# 17_-ETH_CONNECTOR.net
KiCad netlist of a schematic drawn in Altium Designer
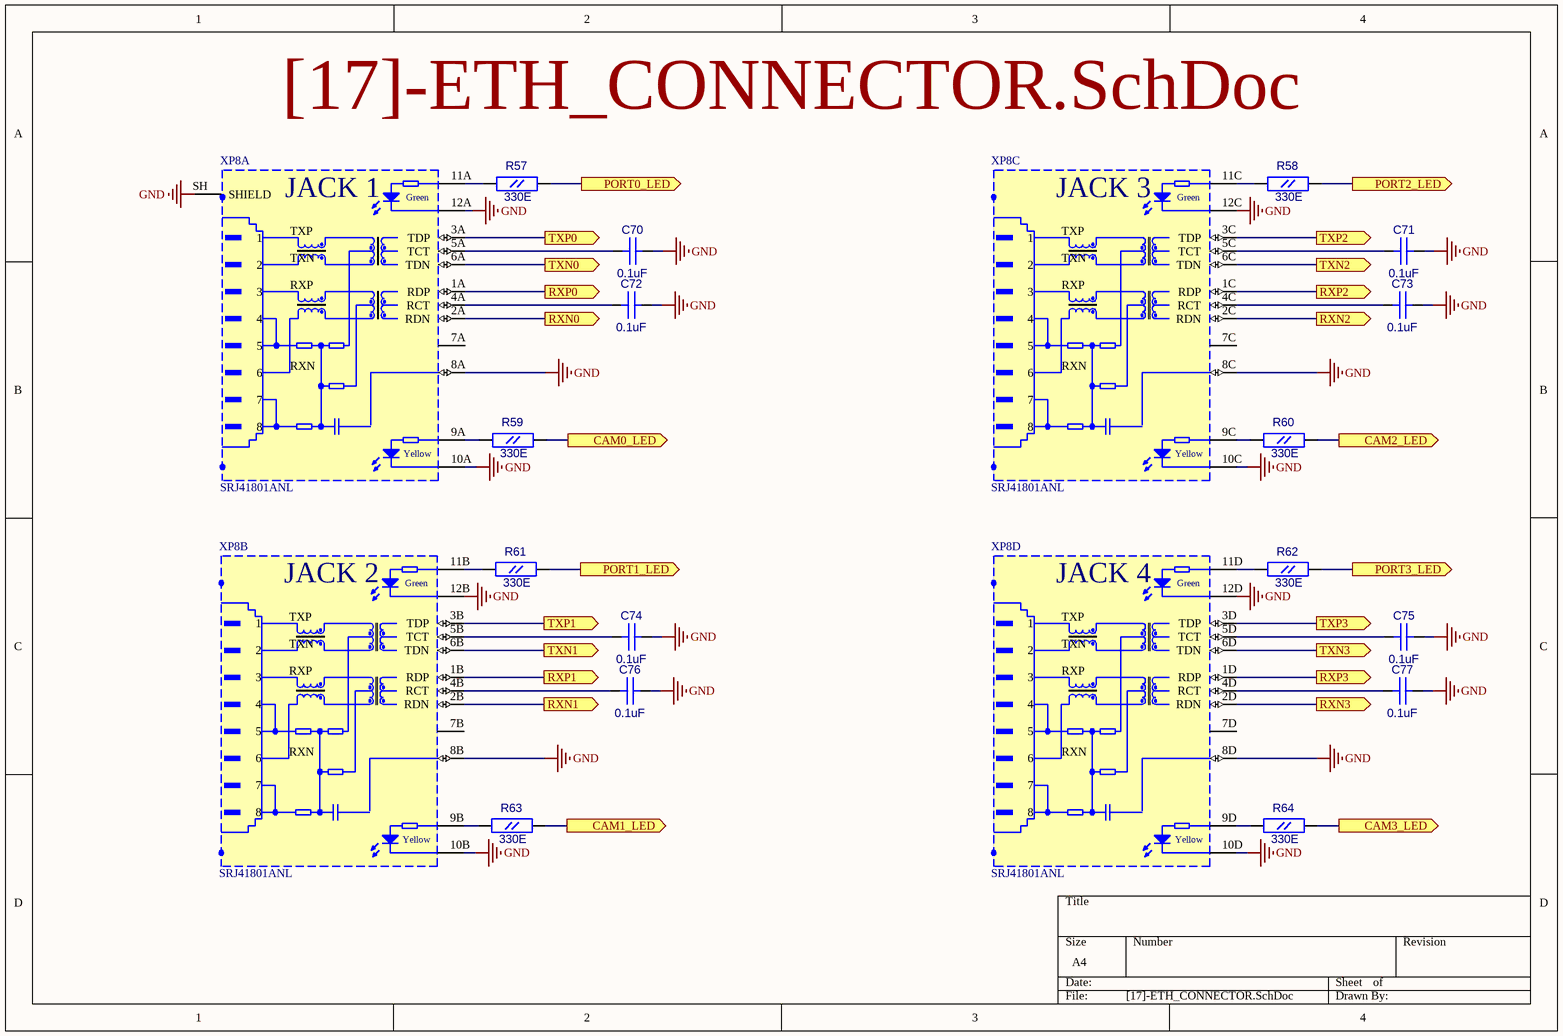
[diagram p0: [17]-ETH_CONNECTOR.SchDoc]

(export (version "E")
  (design (tool "Eeschema 10.0.6"))
  (components
    (comp (ref "C70")
      (value "0.1uF")
      (footprint "CC0603")
      (description "CC0603")
      (libsource (lib "fizik_lib") (part "CC0603"))
    )
    (comp (ref "C71")
      (value "0.1uF")
      (footprint "CC0603")
      (description "CC0603")
      (libsource (lib "fizik_lib") (part "CC0603"))
    )
    (comp (ref "C72")
      (value "0.1uF")
      (footprint "CC0603")
      (description "CC0603")
      (libsource (lib "fizik_lib") (part "CC0603"))
    )
    (comp (ref "C73")
      (value "0.1uF")
      (footprint "CC0603")
      (description "CC0603")
      (libsource (lib "fizik_lib") (part "CC0603"))
    )
    (comp (ref "C74")
      (value "0.1uF")
      (footprint "CC0603")
      (description "CC0603")
      (libsource (lib "fizik_lib") (part "CC0603"))
    )
    (comp (ref "C75")
      (value "0.1uF")
      (footprint "CC0603")
      (description "CC0603")
      (libsource (lib "fizik_lib") (part "CC0603"))
    )
    (comp (ref "C76")
      (value "0.1uF")
      (footprint "CC0603")
      (description "CC0603")
      (libsource (lib "fizik_lib") (part "CC0603"))
    )
    (comp (ref "C77")
      (value "0.1uF")
      (footprint "CC0603")
      (description "CC0603")
      (libsource (lib "fizik_lib") (part "CC0603"))
    )
    (comp (ref "R57")
      (value "330E")
      (footprint "RC0603")
      (description "RC0603")
      (libsource (lib "fizik_lib") (part "RC0603"))
    )
    (comp (ref "R58")
      (value "330E")
      (footprint "RC0603")
      (description "RC0603")
      (libsource (lib "fizik_lib") (part "RC0603"))
    )
    (comp (ref "R59")
      (value "330E")
      (footprint "RC0603")
      (description "RC0603")
      (libsource (lib "fizik_lib") (part "RC0603"))
    )
    (comp (ref "R60")
      (value "330E")
      (footprint "RC0603")
      (description "RC0603")
      (libsource (lib "fizik_lib") (part "RC0603"))
    )
    (comp (ref "R61")
      (value "330E")
      (footprint "RC0603")
      (description "RC0603")
      (libsource (lib "fizik_lib") (part "RC0603"))
    )
    (comp (ref "R62")
      (value "330E")
      (footprint "RC0603")
      (description "RC0603")
      (libsource (lib "fizik_lib") (part "RC0603"))
    )
    (comp (ref "R63")
      (value "330E")
      (footprint "RC0603")
      (description "RC0603")
      (libsource (lib "fizik_lib") (part "RC0603"))
    )
    (comp (ref "R64")
      (value "330E")
      (footprint "RC0603")
      (description "RC0603")
      (libsource (lib "fizik_lib") (part "RC0603"))
    )
    (comp (ref "XP8")
      (value "SRJ41801ANL")
      (footprint "ETHERNET_RJ45_4PORTS")
      (description "4 Ports RJ45 Ethernet connector")
      (libsource (lib "fizik_lib") (part "SRJ41801ANL"))
    )
  )
  (nets
    (net (code "1") (name "/CAM0_LED") (class "Default")
      (node (ref "R59") (pin "2") (pinfunction "B_2") (pintype "passive"))
    )
    (net (code "2") (name "/CAM1_LED") (class "Default")
      (node (ref "R63") (pin "2") (pinfunction "B_2") (pintype "passive"))
    )
    (net (code "3") (name "/CAM2_LED") (class "Default")
      (node (ref "R60") (pin "2") (pinfunction "B_2") (pintype "passive"))
    )
    (net (code "4") (name "/CAM3_LED") (class "Default")
      (node (ref "R64") (pin "2") (pinfunction "B_2") (pintype "passive"))
    )
    (net (code "5") (name "/PORT0_LED") (class "Default")
      (node (ref "R57") (pin "2") (pinfunction "B_2") (pintype "passive"))
    )
    (net (code "6") (name "/PORT1_LED") (class "Default")
      (node (ref "R61") (pin "2") (pinfunction "B_2") (pintype "passive"))
    )
    (net (code "7") (name "/PORT2_LED") (class "Default")
      (node (ref "R58") (pin "2") (pinfunction "B_2") (pintype "passive"))
    )
    (net (code "8") (name "/PORT3_LED") (class "Default")
      (node (ref "R62") (pin "2") (pinfunction "B_2") (pintype "passive"))
    )
    (net (code "9") (name "/RXN0") (class "Default")
      (node (ref "XP8") (pin "2A") (pinfunction "RDN_2A") (pintype "bidirectional"))
    )
    (net (code "10") (name "/RXN1") (class "Default")
      (node (ref "XP8") (pin "2B") (pinfunction "RDN_2B") (pintype "bidirectional"))
    )
    (net (code "11") (name "/RXN2") (class "Default")
      (node (ref "XP8") (pin "2C") (pinfunction "RDN_2C") (pintype "bidirectional"))
    )
    (net (code "12") (name "/RXN3") (class "Default")
      (node (ref "XP8") (pin "2D") (pinfunction "RDN_2D") (pintype "bidirectional"))
    )
    (net (code "13") (name "/RXP0") (class "Default")
      (node (ref "XP8") (pin "1A") (pinfunction "RDP_1A") (pintype "bidirectional"))
    )
    (net (code "14") (name "/RXP1") (class "Default")
      (node (ref "XP8") (pin "1B") (pinfunction "RDP_1B") (pintype "bidirectional"))
    )
    (net (code "15") (name "/RXP2") (class "Default")
      (node (ref "XP8") (pin "1C") (pinfunction "RDP_1C") (pintype "bidirectional"))
    )
    (net (code "16") (name "/RXP3") (class "Default")
      (node (ref "XP8") (pin "1D") (pinfunction "RDP_1D") (pintype "bidirectional"))
    )
    (net (code "17") (name "/TXN0") (class "Default")
      (node (ref "XP8") (pin "6A") (pinfunction "TDN_6A") (pintype "bidirectional"))
    )
    (net (code "18") (name "/TXN1") (class "Default")
      (node (ref "XP8") (pin "6B") (pinfunction "TDN_6B") (pintype "bidirectional"))
    )
    (net (code "19") (name "/TXN2") (class "Default")
      (node (ref "XP8") (pin "6C") (pinfunction "TDN_6C") (pintype "bidirectional"))
    )
    (net (code "20") (name "/TXN3") (class "Default")
      (node (ref "XP8") (pin "6D") (pinfunction "TDN_6D") (pintype "bidirectional"))
    )
    (net (code "21") (name "/TXP0") (class "Default")
      (node (ref "XP8") (pin "3A") (pinfunction "TDP_3A") (pintype "bidirectional"))
    )
    (net (code "22") (name "/TXP1") (class "Default")
      (node (ref "XP8") (pin "3B") (pinfunction "TDP_3B") (pintype "bidirectional"))
    )
    (net (code "23") (name "/TXP2") (class "Default")
      (node (ref "XP8") (pin "3C") (pinfunction "TDP_3C") (pintype "bidirectional"))
    )
    (net (code "24") (name "/TXP3") (class "Default")
      (node (ref "XP8") (pin "3D") (pinfunction "TDP_3D") (pintype "bidirectional"))
    )
    (net (code "25") (name "GND") (class "Default")
      (node (ref "C70") (pin "2") (pinfunction "B_2") (pintype "passive"))
      (node (ref "C71") (pin "2") (pinfunction "B_2") (pintype "passive"))
      (node (ref "C72") (pin "2") (pinfunction "B_2") (pintype "passive"))
      (node (ref "C73") (pin "2") (pinfunction "B_2") (pintype "passive"))
      (node (ref "C74") (pin "2") (pinfunction "B_2") (pintype "passive"))
      (node (ref "C75") (pin "2") (pinfunction "B_2") (pintype "passive"))
      (node (ref "C76") (pin "2") (pinfunction "B_2") (pintype "passive"))
      (node (ref "C77") (pin "2") (pinfunction "B_2") (pintype "passive"))
      (node (ref "XP8") (pin "10A") (pinfunction "D4_10A") (pintype "passive"))
      (node (ref "XP8") (pin "10B") (pinfunction "D4_10B") (pintype "passive"))
      (node (ref "XP8") (pin "10C") (pinfunction "D4_10C") (pintype "passive"))
      (node (ref "XP8") (pin "10D") (pinfunction "D4_10D") (pintype "passive"))
      (node (ref "XP8") (pin "12A") (pinfunction "D2_12A") (pintype "passive"))
      (node (ref "XP8") (pin "12B") (pinfunction "D2_12B") (pintype "passive"))
      (node (ref "XP8") (pin "12C") (pinfunction "D2_12C") (pintype "passive"))
      (node (ref "XP8") (pin "12D") (pinfunction "D2_12D") (pintype "passive"))
      (node (ref "XP8") (pin "8A") (pinfunction "8_8A") (pintype "bidirectional"))
      (node (ref "XP8") (pin "8B") (pinfunction "8_8B") (pintype "bidirectional"))
      (node (ref "XP8") (pin "8C") (pinfunction "8_8C") (pintype "bidirectional"))
      (node (ref "XP8") (pin "8D") (pinfunction "8_8D") (pintype "bidirectional"))
      (node (ref "XP8") (pin "SH") (pinfunction "SHIELD_SH") (pintype "power_in"))
    )
    (net (code "26") (name "Net-(C70-A)") (class "Default")
      (node (ref "C70") (pin "1") (pinfunction "A_1") (pintype "passive"))
      (node (ref "XP8") (pin "5A") (pinfunction "TCT_5A") (pintype "bidirectional"))
    )
    (net (code "27") (name "Net-(C71-A)") (class "Default")
      (node (ref "C71") (pin "1") (pinfunction "A_1") (pintype "passive"))
      (node (ref "XP8") (pin "5C") (pinfunction "TCT_5C") (pintype "bidirectional"))
    )
    (net (code "28") (name "Net-(C72-A)") (class "Default")
      (node (ref "C72") (pin "1") (pinfunction "A_1") (pintype "passive"))
      (node (ref "XP8") (pin "4A") (pinfunction "RCT_4A") (pintype "bidirectional"))
    )
    (net (code "29") (name "Net-(C73-A)") (class "Default")
      (node (ref "C73") (pin "1") (pinfunction "A_1") (pintype "passive"))
      (node (ref "XP8") (pin "4C") (pinfunction "RCT_4C") (pintype "bidirectional"))
    )
    (net (code "30") (name "Net-(C74-A)") (class "Default")
      (node (ref "C74") (pin "1") (pinfunction "A_1") (pintype "passive"))
      (node (ref "XP8") (pin "5B") (pinfunction "TCT_5B") (pintype "bidirectional"))
    )
    (net (code "31") (name "Net-(C75-A)") (class "Default")
      (node (ref "C75") (pin "1") (pinfunction "A_1") (pintype "passive"))
      (node (ref "XP8") (pin "5D") (pinfunction "TCT_5D") (pintype "bidirectional"))
    )
    (net (code "32") (name "Net-(C76-A)") (class "Default")
      (node (ref "C76") (pin "1") (pinfunction "A_1") (pintype "passive"))
      (node (ref "XP8") (pin "4B") (pinfunction "RCT_4B") (pintype "bidirectional"))
    )
    (net (code "33") (name "Net-(C77-A)") (class "Default")
      (node (ref "C77") (pin "1") (pinfunction "A_1") (pintype "passive"))
      (node (ref "XP8") (pin "4D") (pinfunction "RCT_4D") (pintype "bidirectional"))
    )
    (net (code "34") (name "Net-(R57-A)") (class "Default")
      (node (ref "R57") (pin "1") (pinfunction "A_1") (pintype "passive"))
      (node (ref "XP8") (pin "11A") (pinfunction "D1_11A") (pintype "passive"))
    )
    (net (code "35") (name "Net-(R58-A)") (class "Default")
      (node (ref "R58") (pin "1") (pinfunction "A_1") (pintype "passive"))
      (node (ref "XP8") (pin "11C") (pinfunction "D1_11C") (pintype "passive"))
    )
    (net (code "36") (name "Net-(R59-A)") (class "Default")
      (node (ref "R59") (pin "1") (pinfunction "A_1") (pintype "passive"))
      (node (ref "XP8") (pin "9A") (pinfunction "D3_9A") (pintype "passive"))
    )
    (net (code "37") (name "Net-(R60-A)") (class "Default")
      (node (ref "R60") (pin "1") (pinfunction "A_1") (pintype "passive"))
      (node (ref "XP8") (pin "9C") (pinfunction "D3_9C") (pintype "passive"))
    )
    (net (code "38") (name "Net-(R61-A)") (class "Default")
      (node (ref "R61") (pin "1") (pinfunction "A_1") (pintype "passive"))
      (node (ref "XP8") (pin "11B") (pinfunction "D1_11B") (pintype "passive"))
    )
    (net (code "39") (name "Net-(R62-A)") (class "Default")
      (node (ref "R62") (pin "1") (pinfunction "A_1") (pintype "passive"))
      (node (ref "XP8") (pin "11D") (pinfunction "D1_11D") (pintype "passive"))
    )
    (net (code "40") (name "Net-(R63-A)") (class "Default")
      (node (ref "R63") (pin "1") (pinfunction "A_1") (pintype "passive"))
      (node (ref "XP8") (pin "9B") (pinfunction "D3_9B") (pintype "passive"))
    )
    (net (code "41") (name "Net-(R64-A)") (class "Default")
      (node (ref "R64") (pin "1") (pinfunction "A_1") (pintype "passive"))
      (node (ref "XP8") (pin "9D") (pinfunction "D3_9D") (pintype "passive"))
    )
    (net (code "42") (name "unconnected-(XP8A-7-Pad7A)") (class "Default")
      (node (ref "XP8") (pin "7A") (pinfunction "7_7A") (pintype "passive"))
    )
    (net (code "43") (name "unconnected-(XP8B-7-Pad7B)") (class "Default")
      (node (ref "XP8") (pin "7B") (pinfunction "7_7B") (pintype "passive"))
    )
    (net (code "44") (name "unconnected-(XP8C-7-Pad7C)") (class "Default")
      (node (ref "XP8") (pin "7C") (pinfunction "7_7C") (pintype "passive"))
    )
    (net (code "45") (name "unconnected-(XP8D-7-Pad7D)") (class "Default")
      (node (ref "XP8") (pin "7D") (pinfunction "7_7D") (pintype "passive"))
    )
  )
)
